# Sheet1.net
KiCad netlist of a schematic drawn in Altium Designer
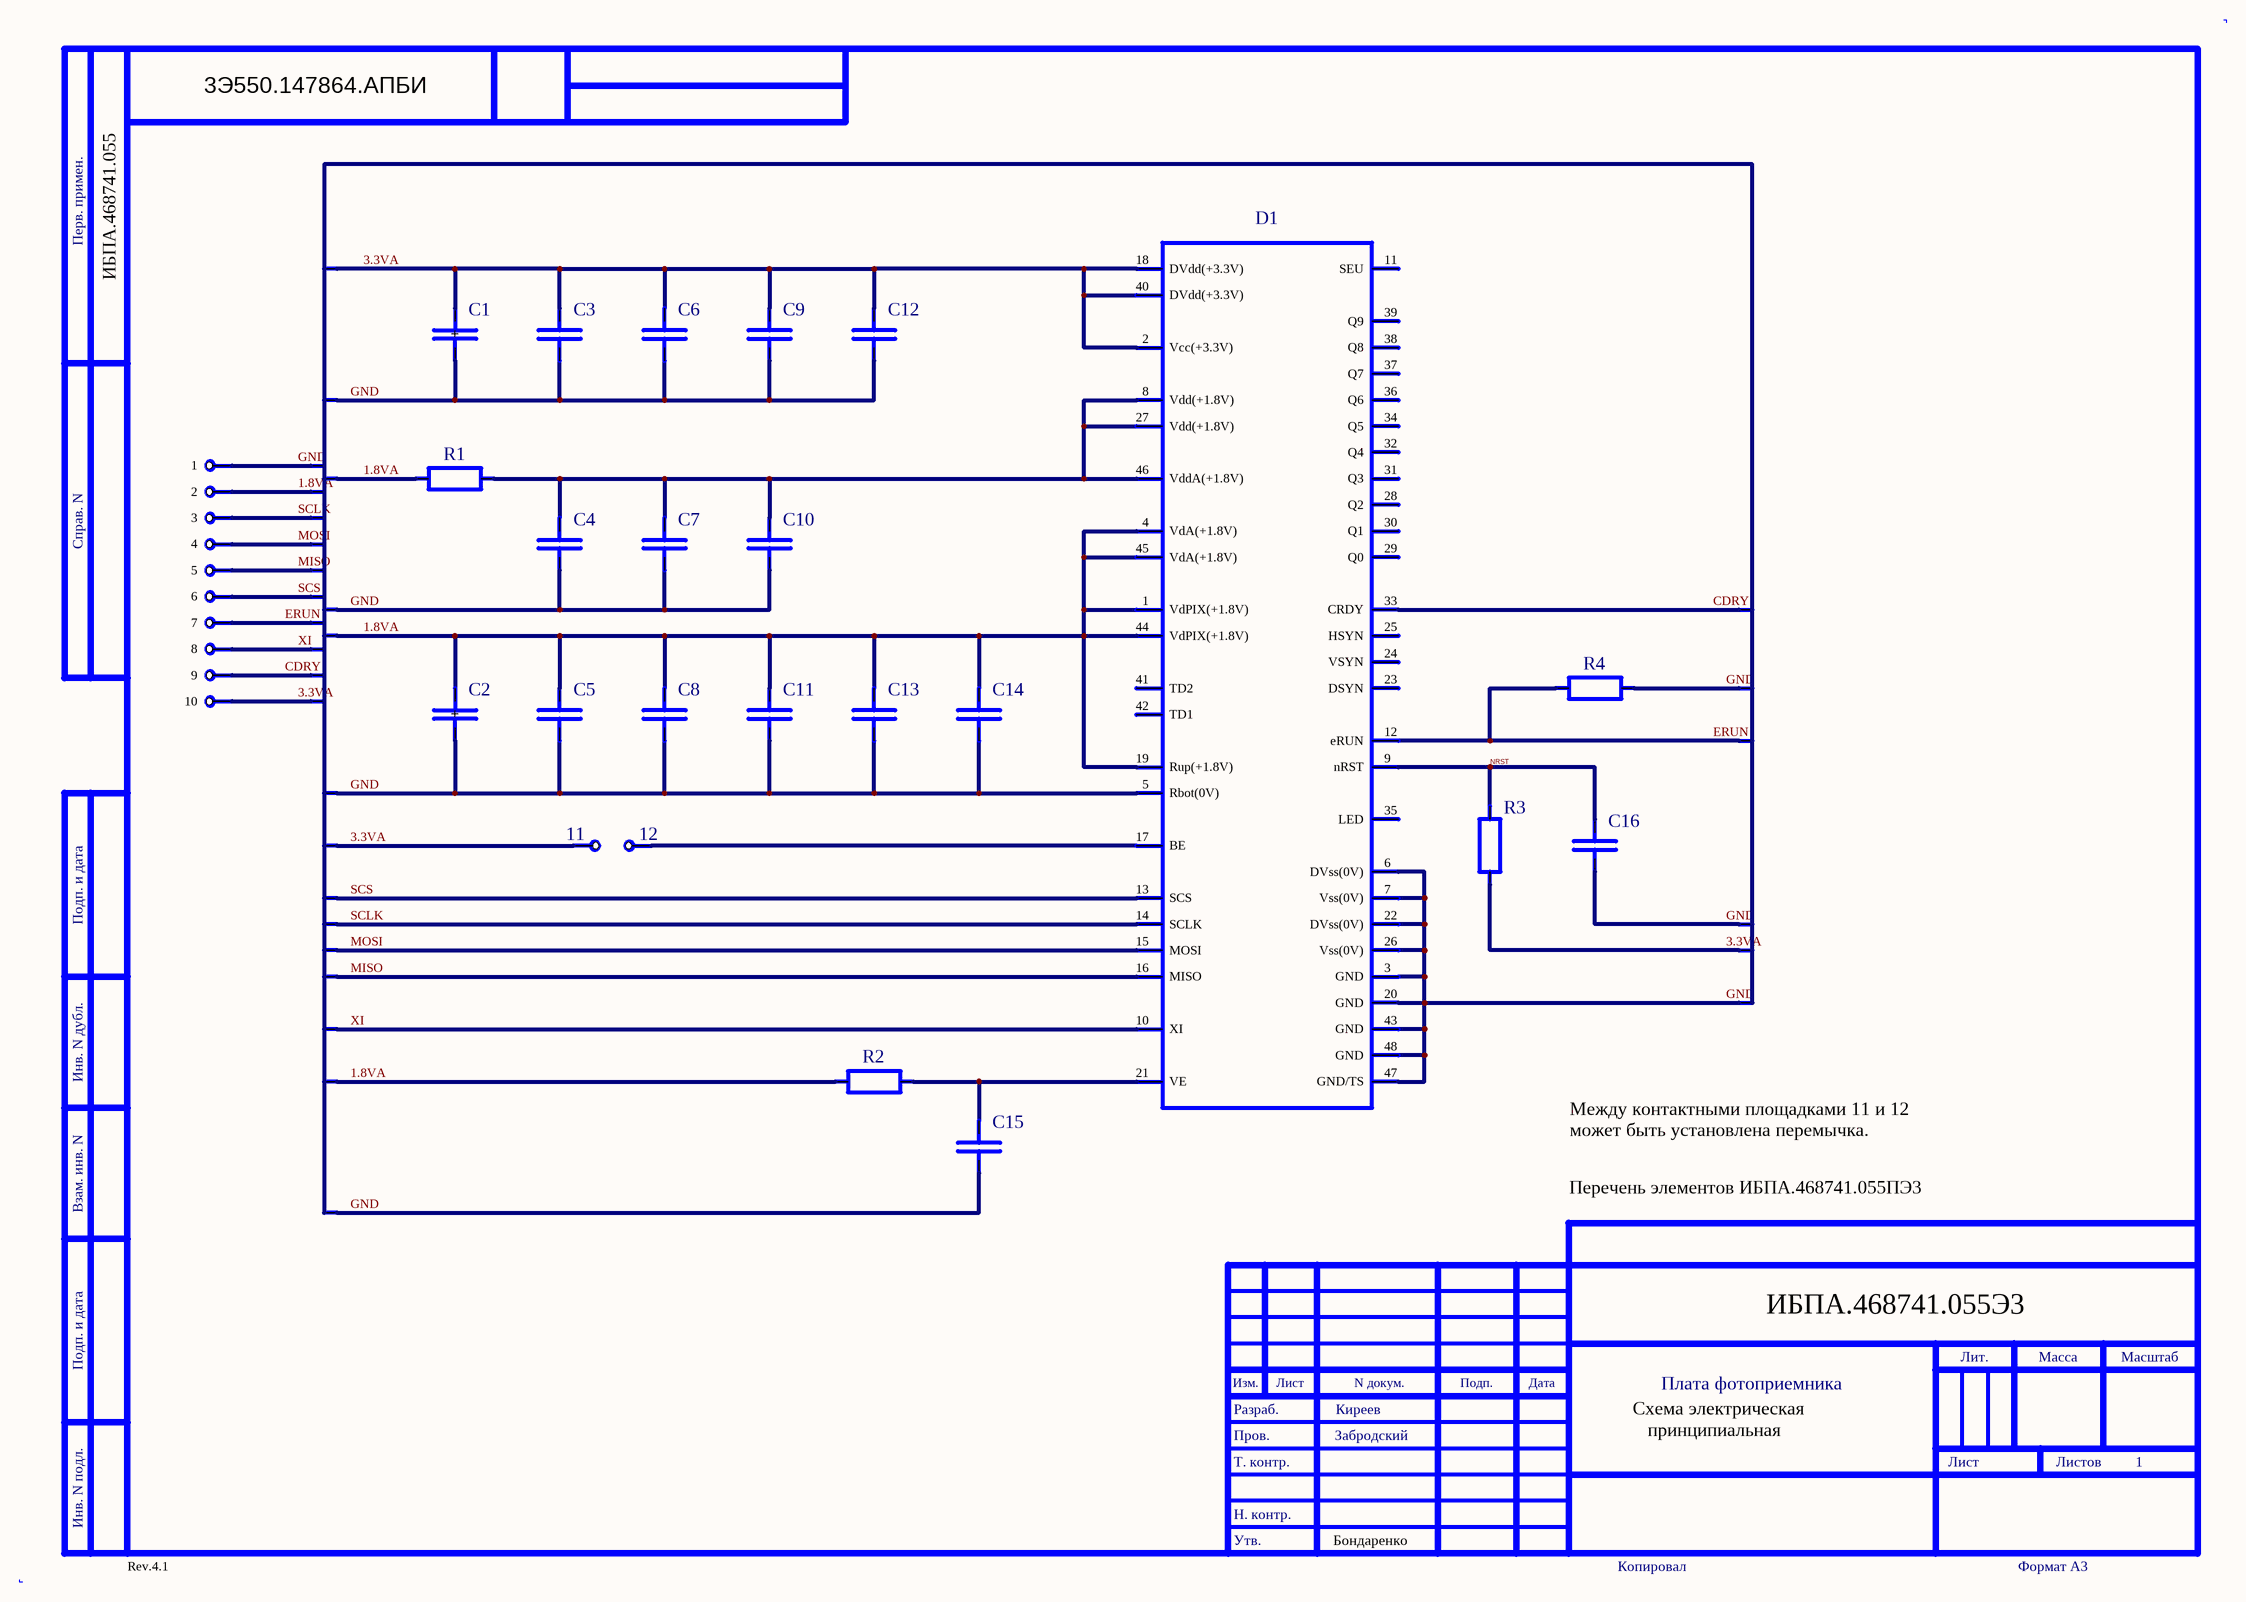
[diagram p0: Sheet1.SCHDOC]

(export (version "E")
  (design (tool "Eeschema 10.0.6"))
  (components
    (comp (ref "11")
      (value "CONT_D1.0(0.6)MM")
      (footprint "CONT_D1.0(0.6)MM")
      (libsource (lib "*") (part "CONT_D1.0(0.6)MM"))
    )
    (comp (ref "12")
      (value "CONT_D1.0(0.6)MM")
      (footprint "CONT_D1.0(0.6)MM")
      (libsource (lib "*") (part "CONT_D1.0(0.6)MM"))
    )
    (comp (ref "C1")
      (value "K53-56A_3628M_2B")
      (footprint "CE_3628M_B")
      (description "{Description}")
      (fields (field (name "PART NUMBER") "ОСМ К53-56А - 10 В - 10 мкФ ±10 % - В"))
      (libsource (lib "*") (part "K53-56A_3628M_2B"))
    )
    (comp (ref "C2")
      (value "K53-56A_3628M_2B")
      (footprint "CE_3628M_B")
      (description "{Description}")
      (fields (field (name "PART NUMBER") "ОСМ К53-56А - 10 В - 10 мкФ ±10 % - В"))
      (libsource (lib "*") (part "K53-56A_3628M_2B"))
    )
    (comp (ref "C3")
      (value "K10-84B_1608M_I")
      (footprint "1608M_I")
      (description "{Description}")
      (fields (field (name "PART NUMBER") "К10-84в - 1608М - 16 В - Н90 - 0,01 мкФ"))
      (libsource (lib "*") (part "K10-84B_1608M_I"))
    )
    (comp (ref "C4")
      (value "K10-84B_2012M_IV")
      (footprint "2012M_IV")
      (description "{Description}")
      (fields (field (name "PART NUMBER") "К10-84в - 2012М - 25 В - Н90 - 0,1 мкФ"))
      (libsource (lib "*") (part "K10-84B_2012M_IV"))
    )
    (comp (ref "C5")
      (value "K10-84B_2012M_IV")
      (footprint "2012M_IV")
      (description "{Description}")
      (fields (field (name "PART NUMBER") "К10-84в - 2012М - 25 В - Н90 - 0,1 мкФ"))
      (libsource (lib "*") (part "K10-84B_2012M_IV"))
    )
    (comp (ref "C6")
      (value "K10-84B_2012M_IV")
      (footprint "2012M_IV")
      (description "{Description}")
      (fields (field (name "PART NUMBER") "К10-84в - 2012М - 25 В - Н90 - 0,1 мкФ"))
      (libsource (lib "*") (part "K10-84B_2012M_IV"))
    )
    (comp (ref "C7")
      (value "K10-84B_2012M_IV")
      (footprint "2012M_IV")
      (description "{Description}")
      (fields (field (name "PART NUMBER") "К10-84в - 2012М - 25 В - Н90 - 0,1 мкФ"))
      (libsource (lib "*") (part "K10-84B_2012M_IV"))
    )
    (comp (ref "C8")
      (value "K10-84B_2012M_IV")
      (footprint "2012M_IV")
      (description "{Description}")
      (fields (field (name "PART NUMBER") "К10-84в - 2012М - 25 В - Н90 - 0,1 мкФ"))
      (libsource (lib "*") (part "K10-84B_2012M_IV"))
    )
    (comp (ref "C9")
      (value "K10-84B_2012M_IV")
      (footprint "2012M_IV")
      (description "{Description}")
      (fields (field (name "PART NUMBER") "К10-84в - 2012М - 25 В - Н90 - 0,1 мкФ"))
      (libsource (lib "*") (part "K10-84B_2012M_IV"))
    )
    (comp (ref "C10")
      (value "K10-84B_2012M_IV")
      (footprint "2012M_IV")
      (description "{Description}")
      (fields (field (name "PART NUMBER") "К10-84в - 2012М - 25 В - Н90 - 0,1 мкФ"))
      (libsource (lib "*") (part "K10-84B_2012M_IV"))
    )
    (comp (ref "C11")
      (value "K10-84B_2012M_IV")
      (footprint "2012M_IV")
      (description "{Description}")
      (fields (field (name "PART NUMBER") "К10-84в - 2012М - 25 В - Н90 - 0,1 мкФ"))
      (libsource (lib "*") (part "K10-84B_2012M_IV"))
    )
    (comp (ref "C12")
      (value "K10-84B_2012M_IV")
      (footprint "2012M_IV")
      (description "{Description}")
      (fields (field (name "PART NUMBER") "К10-84в - 2012М - 25 В - Н90 - 0,1 мкФ"))
      (libsource (lib "*") (part "K10-84B_2012M_IV"))
    )
    (comp (ref "C13")
      (value "K10-84B_2012M_IV")
      (footprint "2012M_IV")
      (description "{Description}")
      (fields (field (name "PART NUMBER") "К10-84в - 2012М - 25 В - Н90 - 0,1 мкФ"))
      (libsource (lib "*") (part "K10-84B_2012M_IV"))
    )
    (comp (ref "C14")
      (value "K10-84B_2012M_IV")
      (footprint "2012M_IV")
      (description "{Description}")
      (fields (field (name "PART NUMBER") "К10-84в - 2012М - 25 В - Н90 - 0,1 мкФ"))
      (libsource (lib "*") (part "K10-84B_2012M_IV"))
    )
    (comp (ref "C15")
      (value "K10-84B_2012M_IV")
      (footprint "2012M_IV")
      (description "{Description}")
      (fields (field (name "PART NUMBER") "К10-84в - 2012М - 25 В - Н90 - 0,1 мкФ"))
      (libsource (lib "*") (part "K10-84B_2012M_IV"))
    )
    (comp (ref "C16")
      (value "K10-84B_2012M_IV")
      (footprint "2012M_IV")
      (description "{Description}")
      (fields (field (name "PART NUMBER") "К10-84в - 2012М - 25 В - Н90 - 0,1 мкФ"))
      (libsource (lib "*") (part "K10-84B_2012M_IV"))
    )
    (comp (ref "D1")
      (value "UIC1203R")
      (footprint "CERAMIC_JLCC-48")
      (description "{Description}")
      (fields (field (name "PART NUMBER") "UI1203R"))
      (libsource (lib "*") (part "UIC1203R"))
    )
    (comp (ref "OFF1") (value "BUS_CONNECTOR") (libsource (lib "*") (part "BUS_CONNECTOR")))
    (comp (ref "OFF2")
      (value "BUS_CONNECTOR")
      (description "BUS_CONNECTOR_VARIANT_1")
      (libsource (lib "*") (part "BUS_CONNECTOR"))
    )
    (comp (ref "OFF3")
      (value "BUS_CONNECTOR")
      (description "BUS_CONNECTOR_VARIANT_2")
      (libsource (lib "*") (part "BUS_CONNECTOR"))
    )
    (comp (ref "OFF4")
      (value "BUS_CONNECTOR")
      (description "BUS_CONNECTOR_VARIANT_2")
      (libsource (lib "*") (part "BUS_CONNECTOR"))
    )
    (comp (ref "OFF5")
      (value "BUS_CONNECTOR")
      (description "BUS_CONNECTOR_VARIANT_2")
      (libsource (lib "*") (part "BUS_CONNECTOR"))
    )
    (comp (ref "OFF6")
      (value "BUS_CONNECTOR")
      (description "BUS_CONNECTOR_VARIANT_2")
      (libsource (lib "*") (part "BUS_CONNECTOR"))
    )
    (comp (ref "OFF7")
      (value "BUS_CONNECTOR")
      (description "BUS_CONNECTOR_VARIANT_2")
      (libsource (lib "*") (part "BUS_CONNECTOR"))
    )
    (comp (ref "OFF8")
      (value "BUS_CONNECTOR")
      (description "BUS_CONNECTOR_VARIANT_2")
      (libsource (lib "*") (part "BUS_CONNECTOR"))
    )
    (comp (ref "OFF9")
      (value "BUS_CONNECTOR")
      (description "BUS_CONNECTOR_VARIANT_2")
      (libsource (lib "*") (part "BUS_CONNECTOR"))
    )
    (comp (ref "OFF10")
      (value "BUS_CONNECTOR")
      (description "BUS_CONNECTOR_VARIANT_1")
      (libsource (lib "*") (part "BUS_CONNECTOR"))
    )
    (comp (ref "OFF11")
      (value "BUS_CONNECTOR")
      (description "BUS_CONNECTOR_VARIANT_1")
      (libsource (lib "*") (part "BUS_CONNECTOR"))
    )
    (comp (ref "OFF12") (value "BUS_CONNECTOR") (libsource (lib "*") (part "BUS_CONNECTOR")))
    (comp (ref "OFF13")
      (value "BUS_CONNECTOR")
      (description "BUS_CONNECTOR_VARIANT_1")
      (libsource (lib "*") (part "BUS_CONNECTOR"))
    )
    (comp (ref "OFF14") (value "BUS_CONNECTOR") (libsource (lib "*") (part "BUS_CONNECTOR")))
    (comp (ref "OFF15")
      (value "BUS_CONNECTOR")
      (description "BUS_CONNECTOR_VARIANT_1")
      (libsource (lib "*") (part "BUS_CONNECTOR"))
    )
    (comp (ref "OFF16") (value "BUS_CONNECTOR") (libsource (lib "*") (part "BUS_CONNECTOR")))
    (comp (ref "OFF17")
      (value "BUS_CONNECTOR")
      (description "BUS_CONNECTOR_VARIANT_2")
      (libsource (lib "*") (part "BUS_CONNECTOR"))
    )
    (comp (ref "OFF18")
      (value "BUS_CONNECTOR")
      (description "BUS_CONNECTOR_VARIANT_2")
      (libsource (lib "*") (part "BUS_CONNECTOR"))
    )
    (comp (ref "OFF19")
      (value "BUS_CONNECTOR")
      (description "BUS_CONNECTOR_VARIANT_2")
      (libsource (lib "*") (part "BUS_CONNECTOR"))
    )
    (comp (ref "OFF20")
      (value "BUS_CONNECTOR")
      (description "BUS_CONNECTOR_VARIANT_2")
      (libsource (lib "*") (part "BUS_CONNECTOR"))
    )
    (comp (ref "OFF21")
      (value "BUS_CONNECTOR")
      (description "BUS_CONNECTOR_VARIANT_2")
      (libsource (lib "*") (part "BUS_CONNECTOR"))
    )
    (comp (ref "OFF22")
      (value "BUS_CONNECTOR")
      (description "BUS_CONNECTOR_VARIANT_1")
      (libsource (lib "*") (part "BUS_CONNECTOR"))
    )
    (comp (ref "OFF23")
      (value "BUS_CONNECTOR")
      (description "BUS_CONNECTOR_VARIANT_2")
      (libsource (lib "*") (part "BUS_CONNECTOR"))
    )
    (comp (ref "OFF24") (value "BUS_CONNECTOR") (libsource (lib "*") (part "BUS_CONNECTOR")))
    (comp (ref "OFF25")
      (value "BUS_CONNECTOR")
      (description "BUS_CONNECTOR_VARIANT_2")
      (libsource (lib "*") (part "BUS_CONNECTOR"))
    )
    (comp (ref "OFF26") (value "BUS_CONNECTOR") (libsource (lib "*") (part "BUS_CONNECTOR")))
    (comp (ref "OFF27")
      (value "BUS_CONNECTOR")
      (description "BUS_CONNECTOR_VARIANT_1")
      (libsource (lib "*") (part "BUS_CONNECTOR"))
    )
    (comp (ref "OFF28") (value "BUS_CONNECTOR") (libsource (lib "*") (part "BUS_CONNECTOR")))
    (comp (ref "OFF29") (value "BUS_CONNECTOR") (libsource (lib "*") (part "BUS_CONNECTOR")))
    (comp (ref "OFF30")
      (value "BUS_CONNECTOR")
      (description "BUS_CONNECTOR_VARIANT_1")
      (libsource (lib "*") (part "BUS_CONNECTOR"))
    )
    (comp (ref "R1")
      (value "P1-12-0,125_2012M")
      (footprint "R1-12_2012M_0805")
      (description "{Description}")
      (fields (field (name "PART NUMBER") "ОСМ Р1-12 - 0,125 - 75 Ом ±5% - М - А"))
      (libsource (lib "*") (part "P1-12-0,125_2012M"))
    )
    (comp (ref "R2")
      (value "P1-12-0,125_2012M")
      (footprint "R1-12_2012M_0805")
      (description "{Description}")
      (fields (field (name "PART NUMBER") "ОСМ Р1-12 - 0,125 - 1 кОм ±5% - М - А"))
      (libsource (lib "*") (part "P1-12-0,125_2012M"))
    )
    (comp (ref "R3")
      (value "P1-12-0,125_2012M")
      (footprint "R1-12_2012M_0805")
      (description "{Description}")
      (fields (field (name "PART NUMBER") "ОСМ Р1-12 - 0,125 - 3 кОм ±5% - М - А"))
      (libsource (lib "*") (part "P1-12-0,125_2012M"))
    )
    (comp (ref "R4")
      (value "P1-12-0,125_2012M")
      (footprint "R1-12_2012M_0805")
      (description "{Description}")
      (fields (field (name "PART NUMBER") "ОСМ Р1-12 - 0,125 - 20 кОм ±5% - М - А"))
      (libsource (lib "*") (part "P1-12-0,125_2012M"))
    )
    (comp (ref "TP1")
      (value "TMM-105-01-T-D")
      (footprint "TMM-105-01-G-D_SAMTEC")
      (description "{Description}")
      (fields (field (name "PART NUMBER") "{Part Number}"))
      (libsource (lib "*") (part "TMM-105-01-T-D"))
    )
  )
  (nets
    (net (code "1") (name "/1.8VA") (class "Default")
      (node (ref "C11") (pin "1") (pinfunction "1_1") (pintype "passive"))
      (node (ref "C13") (pin "1") (pinfunction "1_1") (pintype "passive"))
      (node (ref "C14") (pin "1") (pinfunction "1_1") (pintype "passive"))
      (node (ref "C2") (pin "1") (pinfunction "+_1") (pintype "passive"))
      (node (ref "C5") (pin "1") (pinfunction "1_1") (pintype "passive"))
      (node (ref "C8") (pin "1") (pinfunction "1_1") (pintype "passive"))
      (node (ref "D1") (pin "1") (pinfunction "VdPIX(+1.8V)_1") (pintype "passive"))
      (node (ref "D1") (pin "19") (pinfunction "Rup(+1.8V)_19") (pintype "passive"))
      (node (ref "D1") (pin "4") (pinfunction "VdA(+1.8V)_4") (pintype "passive"))
      (node (ref "D1") (pin "44") (pinfunction "VdPIX(+1.8V)_44") (pintype "passive"))
      (node (ref "D1") (pin "45") (pinfunction "VdA(+1.8V)_45") (pintype "passive"))
      (node (ref "OFF13") (pin "1") (pinfunction "1_1") (pintype "passive"))
      (node (ref "OFF15") (pin "1") (pinfunction "1_1") (pintype "passive"))
      (node (ref "OFF2") (pin "1") (pinfunction "1_1") (pintype "passive"))
      (node (ref "OFF22") (pin "1") (pinfunction "1_1") (pintype "passive"))
      (node (ref "R1") (pin "1") (pinfunction "1_1") (pintype "passive"))
      (node (ref "R2") (pin "1") (pinfunction "1_1") (pintype "passive"))
      (node (ref "TP1") (pin "2") (pinfunction "2_2") (pintype "passive"))
    )
    (net (code "2") (name "/3.3VA") (class "Default")
      (node (ref "11") (pin "1") (pinfunction "1_1") (pintype "passive"))
      (node (ref "C1") (pin "1") (pinfunction "+_1") (pintype "passive"))
      (node (ref "C12") (pin "1") (pinfunction "1_1") (pintype "passive"))
      (node (ref "C3") (pin "1") (pinfunction "1_1") (pintype "passive"))
      (node (ref "C6") (pin "1") (pinfunction "1_1") (pintype "passive"))
      (node (ref "C9") (pin "1") (pinfunction "1_1") (pintype "passive"))
      (node (ref "D1") (pin "18") (pinfunction "DVdd(+3.3V)_18") (pintype "passive"))
      (node (ref "D1") (pin "2") (pinfunction "Vcc(+3.3V)_2") (pintype "passive"))
      (node (ref "D1") (pin "40") (pinfunction "DVdd(+3.3V)_40") (pintype "passive"))
      (node (ref "OFF10") (pin "1") (pinfunction "1_1") (pintype "passive"))
      (node (ref "OFF11") (pin "1") (pinfunction "1_1") (pintype "passive"))
      (node (ref "OFF27") (pin "1") (pinfunction "1_1") (pintype "passive"))
      (node (ref "OFF30") (pin "1") (pinfunction "1_1") (pintype "passive"))
      (node (ref "R3") (pin "2") (pinfunction "2_2") (pintype "passive"))
      (node (ref "TP1") (pin "10") (pinfunction "10_10") (pintype "passive"))
    )
    (net (code "3") (name "/CDRY") (class "Default")
      (node (ref "D1") (pin "33") (pinfunction "CRDY_33") (pintype "passive"))
      (node (ref "OFF23") (pin "1") (pinfunction "1_1") (pintype "passive"))
      (node (ref "OFF9") (pin "1") (pinfunction "1_1") (pintype "passive"))
      (node (ref "TP1") (pin "9") (pinfunction "9_9") (pintype "passive"))
    )
    (net (code "4") (name "/ERUN") (class "Default")
      (node (ref "D1") (pin "12") (pinfunction "eRUN_12") (pintype "passive"))
      (node (ref "OFF25") (pin "1") (pinfunction "1_1") (pintype "passive"))
      (node (ref "OFF7") (pin "1") (pinfunction "1_1") (pintype "passive"))
      (node (ref "R4") (pin "1") (pinfunction "1_1") (pintype "passive"))
      (node (ref "TP1") (pin "7") (pinfunction "7_7") (pintype "passive"))
    )
    (net (code "5") (name "/GND") (class "Default")
      (node (ref "C1") (pin "2") (pinfunction "2_2") (pintype "passive"))
      (node (ref "C10") (pin "2") (pinfunction "2_2") (pintype "passive"))
      (node (ref "C11") (pin "2") (pinfunction "2_2") (pintype "passive"))
      (node (ref "C12") (pin "2") (pinfunction "2_2") (pintype "passive"))
      (node (ref "C13") (pin "2") (pinfunction "2_2") (pintype "passive"))
      (node (ref "C14") (pin "2") (pinfunction "2_2") (pintype "passive"))
      (node (ref "C15") (pin "2") (pinfunction "2_2") (pintype "passive"))
      (node (ref "C16") (pin "2") (pinfunction "2_2") (pintype "passive"))
      (node (ref "C2") (pin "2") (pinfunction "2_2") (pintype "passive"))
      (node (ref "C3") (pin "2") (pinfunction "2_2") (pintype "passive"))
      (node (ref "C4") (pin "2") (pinfunction "2_2") (pintype "passive"))
      (node (ref "C5") (pin "2") (pinfunction "2_2") (pintype "passive"))
      (node (ref "C6") (pin "2") (pinfunction "2_2") (pintype "passive"))
      (node (ref "C7") (pin "2") (pinfunction "2_2") (pintype "passive"))
      (node (ref "C8") (pin "2") (pinfunction "2_2") (pintype "passive"))
      (node (ref "C9") (pin "2") (pinfunction "2_2") (pintype "passive"))
      (node (ref "D1") (pin "20") (pinfunction "GND_20") (pintype "passive"))
      (node (ref "D1") (pin "22") (pinfunction "DVss(0V)_22") (pintype "passive"))
      (node (ref "D1") (pin "26") (pinfunction "Vss(0V)_26") (pintype "passive"))
      (node (ref "D1") (pin "3") (pinfunction "GND_3") (pintype "passive"))
      (node (ref "D1") (pin "43") (pinfunction "GND_43") (pintype "passive"))
      (node (ref "D1") (pin "47") (pinfunction "GND/TS_47") (pintype "passive"))
      (node (ref "D1") (pin "48") (pinfunction "GND_48") (pintype "passive"))
      (node (ref "D1") (pin "5") (pinfunction "Rbot(0V)_5") (pintype "passive"))
      (node (ref "D1") (pin "6") (pinfunction "DVss(0V)_6") (pintype "passive"))
      (node (ref "D1") (pin "7") (pinfunction "Vss(0V)_7") (pintype "passive"))
      (node (ref "OFF1") (pin "1") (pinfunction "1_1") (pintype "passive"))
      (node (ref "OFF12") (pin "1") (pinfunction "1_1") (pintype "passive"))
      (node (ref "OFF14") (pin "1") (pinfunction "1_1") (pintype "passive"))
      (node (ref "OFF16") (pin "1") (pinfunction "1_1") (pintype "passive"))
      (node (ref "OFF24") (pin "1") (pinfunction "1_1") (pintype "passive"))
      (node (ref "OFF26") (pin "1") (pinfunction "1_1") (pintype "passive"))
      (node (ref "OFF28") (pin "1") (pinfunction "1_1") (pintype "passive"))
      (node (ref "OFF29") (pin "1") (pinfunction "1_1") (pintype "passive"))
      (node (ref "R4") (pin "2") (pinfunction "2_2") (pintype "passive"))
      (node (ref "TP1") (pin "1") (pinfunction "1_1") (pintype "passive"))
    )
    (net (code "6") (name "/MISO") (class "Default")
      (node (ref "D1") (pin "16") (pinfunction "MISO_16") (pintype "passive"))
      (node (ref "OFF20") (pin "1") (pinfunction "1_1") (pintype "passive"))
      (node (ref "OFF5") (pin "1") (pinfunction "1_1") (pintype "passive"))
      (node (ref "TP1") (pin "5") (pinfunction "5_5") (pintype "passive"))
    )
    (net (code "7") (name "/MOSI") (class "Default")
      (node (ref "D1") (pin "15") (pinfunction "MOSI_15") (pintype "passive"))
      (node (ref "OFF19") (pin "1") (pinfunction "1_1") (pintype "passive"))
      (node (ref "OFF4") (pin "1") (pinfunction "1_1") (pintype "passive"))
      (node (ref "TP1") (pin "4") (pinfunction "4_4") (pintype "passive"))
    )
    (net (code "8") (name "/NRST") (class "Default")
      (node (ref "C16") (pin "1") (pinfunction "1_1") (pintype "passive"))
      (node (ref "D1") (pin "9") (pinfunction "nRST_9") (pintype "passive"))
      (node (ref "R3") (pin "1") (pinfunction "1_1") (pintype "passive"))
    )
    (net (code "9") (name "/SCLK") (class "Default")
      (node (ref "D1") (pin "14") (pinfunction "SCLK_14") (pintype "passive"))
      (node (ref "OFF18") (pin "1") (pinfunction "1_1") (pintype "passive"))
      (node (ref "OFF3") (pin "1") (pinfunction "1_1") (pintype "passive"))
      (node (ref "TP1") (pin "3") (pinfunction "3_3") (pintype "passive"))
    )
    (net (code "10") (name "/SCS") (class "Default")
      (node (ref "D1") (pin "13") (pinfunction "SCS_13") (pintype "passive"))
      (node (ref "OFF17") (pin "1") (pinfunction "1_1") (pintype "passive"))
      (node (ref "OFF6") (pin "1") (pinfunction "1_1") (pintype "passive"))
      (node (ref "TP1") (pin "6") (pinfunction "6_6") (pintype "passive"))
    )
    (net (code "11") (name "/XI") (class "Default")
      (node (ref "D1") (pin "10") (pinfunction "XI_10") (pintype "passive"))
      (node (ref "OFF21") (pin "1") (pinfunction "1_1") (pintype "passive"))
      (node (ref "OFF8") (pin "1") (pinfunction "1_1") (pintype "passive"))
      (node (ref "TP1") (pin "8") (pinfunction "8_8") (pintype "passive"))
    )
    (net (code "12") (name "Net-(D1-BE)") (class "Default")
      (node (ref "12") (pin "1") (pinfunction "1_1") (pintype "passive"))
      (node (ref "D1") (pin "17") (pinfunction "BE_17") (pintype "passive"))
    )
    (net (code "13") (name "Net-(D1-VE)") (class "Default")
      (node (ref "C15") (pin "1") (pinfunction "1_1") (pintype "passive"))
      (node (ref "D1") (pin "21") (pinfunction "VE_21") (pintype "passive"))
      (node (ref "R2") (pin "2") (pinfunction "2_2") (pintype "passive"))
    )
    (net (code "14") (name "Net-(D1-VddA(+1.8V))") (class "Default")
      (node (ref "C10") (pin "1") (pinfunction "1_1") (pintype "passive"))
      (node (ref "C4") (pin "1") (pinfunction "1_1") (pintype "passive"))
      (node (ref "C7") (pin "1") (pinfunction "1_1") (pintype "passive"))
      (node (ref "D1") (pin "27") (pinfunction "Vdd(+1.8V)_27") (pintype "passive"))
      (node (ref "D1") (pin "46") (pinfunction "VddA(+1.8V)_46") (pintype "passive"))
      (node (ref "D1") (pin "8") (pinfunction "Vdd(+1.8V)_8") (pintype "passive"))
      (node (ref "R1") (pin "2") (pinfunction "2_2") (pintype "passive"))
    )
    (net (code "15") (name "unconnected-(D1-DSYN-Pad23)") (class "Default")
      (node (ref "D1") (pin "23") (pinfunction "DSYN_23") (pintype "passive"))
    )
    (net (code "16") (name "unconnected-(D1-HSYN-Pad25)") (class "Default")
      (node (ref "D1") (pin "25") (pinfunction "HSYN_25") (pintype "passive"))
    )
    (net (code "17") (name "unconnected-(D1-LED-Pad35)") (class "Default")
      (node (ref "D1") (pin "35") (pinfunction "LED_35") (pintype "passive"))
    )
    (net (code "18") (name "unconnected-(D1-Q0-Pad29)") (class "Default")
      (node (ref "D1") (pin "29") (pinfunction "Q0_29") (pintype "passive"))
    )
    (net (code "19") (name "unconnected-(D1-Q1-Pad30)") (class "Default")
      (node (ref "D1") (pin "30") (pinfunction "Q1_30") (pintype "passive"))
    )
    (net (code "20") (name "unconnected-(D1-Q2-Pad28)") (class "Default")
      (node (ref "D1") (pin "28") (pinfunction "Q2_28") (pintype "passive"))
    )
    (net (code "21") (name "unconnected-(D1-Q3-Pad31)") (class "Default")
      (node (ref "D1") (pin "31") (pinfunction "Q3_31") (pintype "passive"))
    )
    (net (code "22") (name "unconnected-(D1-Q4-Pad32)") (class "Default")
      (node (ref "D1") (pin "32") (pinfunction "Q4_32") (pintype "passive"))
    )
    (net (code "23") (name "unconnected-(D1-Q5-Pad34)") (class "Default")
      (node (ref "D1") (pin "34") (pinfunction "Q5_34") (pintype "passive"))
    )
    (net (code "24") (name "unconnected-(D1-Q6-Pad36)") (class "Default")
      (node (ref "D1") (pin "36") (pinfunction "Q6_36") (pintype "passive"))
    )
    (net (code "25") (name "unconnected-(D1-Q7-Pad37)") (class "Default")
      (node (ref "D1") (pin "37") (pinfunction "Q7_37") (pintype "passive"))
    )
    (net (code "26") (name "unconnected-(D1-Q8-Pad38)") (class "Default")
      (node (ref "D1") (pin "38") (pinfunction "Q8_38") (pintype "passive"))
    )
    (net (code "27") (name "unconnected-(D1-Q9-Pad39)") (class "Default")
      (node (ref "D1") (pin "39") (pinfunction "Q9_39") (pintype "passive"))
    )
    (net (code "28") (name "unconnected-(D1-SEU-Pad11)") (class "Default")
      (node (ref "D1") (pin "11") (pinfunction "SEU_11") (pintype "passive"))
    )
    (net (code "29") (name "unconnected-(D1-TD1-Pad42)") (class "Default")
      (node (ref "D1") (pin "42") (pinfunction "TD1_42") (pintype "passive"))
    )
    (net (code "30") (name "unconnected-(D1-TD2-Pad41)") (class "Default")
      (node (ref "D1") (pin "41") (pinfunction "TD2_41") (pintype "passive"))
    )
    (net (code "31") (name "unconnected-(D1-VSYN-Pad24)") (class "Default")
      (node (ref "D1") (pin "24") (pinfunction "VSYN_24") (pintype "passive"))
    )
  )
)
